# WL-RF-SWR.net
KiCad netlist of a schematic drawn in Altium Designer
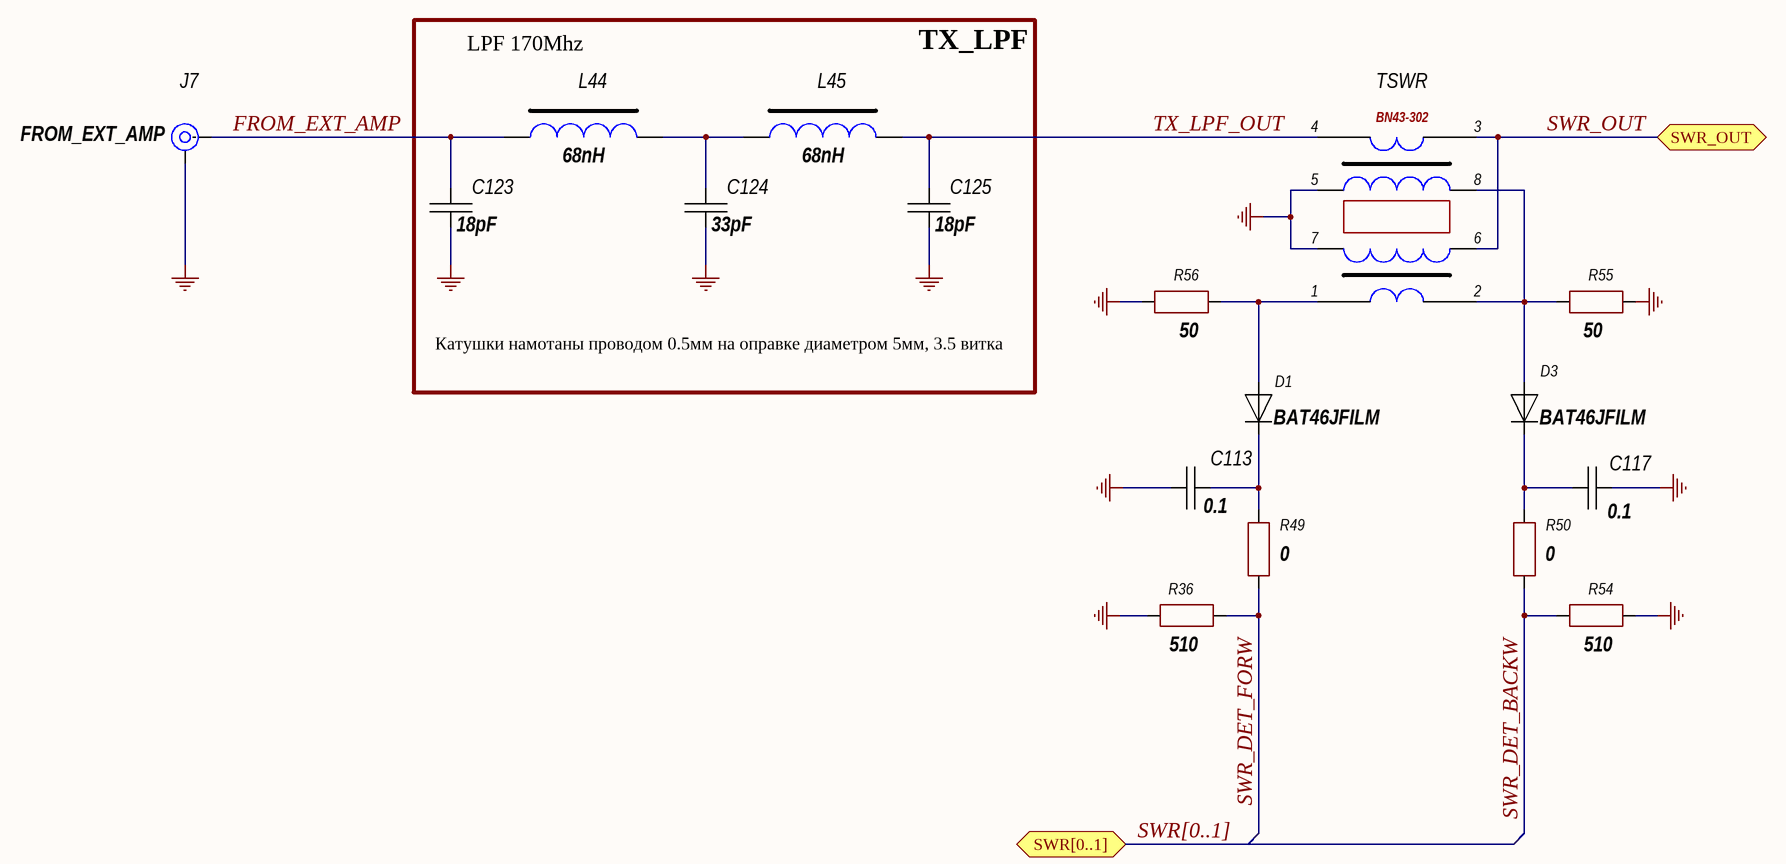
[diagram p0: WL-RF-SWR.SchDoc]

(export (version "E")
  (design (tool "Eeschema 10.0.6"))
  (components
    (comp (ref "C113")
      (value "0.1")
      (footprint "standard:CH0805C")
      (libsource (lib "Discrete") (part "Capacitor"))
    )
    (comp (ref "C117")
      (value "0.1")
      (footprint "standard:CH0805C")
      (libsource (lib "Discrete") (part "Capacitor"))
    )
    (comp (ref "C123")
      (value "18pF")
      (footprint "standard:CH0805C")
      (libsource (lib "Discrete") (part "Capacitor"))
    )
    (comp (ref "C124")
      (value "33pF")
      (footprint "standard:CH0805C")
      (libsource (lib "Discrete") (part "Capacitor"))
    )
    (comp (ref "C125")
      (value "18pF")
      (footprint "standard:CH0805C")
      (libsource (lib "Discrete") (part "Capacitor"))
    )
    (comp (ref "D1") (value "BAT46JFILM") (footprint "D9B") (libsource (lib "Diods") (part "Diod")))
    (comp (ref "D3") (value "BAT46JFILM") (footprint "D9B") (libsource (lib "Diods") (part "Diod")))
    (comp (ref "J7")
      (value "FROM_EXT_AMP")
      (footprint "custom:CON: SMA")
      (description "RF")
      (libsource (lib "Connectors") (part "SMA"))
    )
    (comp (ref "L44") (value "68nH") (libsource (lib "Transformers") (part "TRANS")))
    (comp (ref "L45") (value "68nH") (libsource (lib "Transformers") (part "TRANS")))
    (comp (ref "R36")
      (value "510")
      (footprint "standard:CH1206R")
      (libsource (lib "Discrete") (part "Resistor"))
    )
    (comp (ref "R49")
      (value "0")
      (footprint "standard:CH1206R")
      (libsource (lib "Discrete") (part "Resistor"))
    )
    (comp (ref "R50")
      (value "0")
      (footprint "standard:CH1206R")
      (libsource (lib "Discrete") (part "Resistor"))
    )
    (comp (ref "R54") (value "510") (footprint "standard:CH1206R") (libsource (lib "") (part "Resistor_1")))
    (comp (ref "R55") (value "50") (footprint "standard:CH1206R") (libsource (lib "") (part "Resistor_1")))
    (comp (ref "R56")
      (value "50")
      (footprint "standard:CH1206R")
      (libsource (lib "Discrete") (part "Resistor"))
    )
    (comp (ref "TSWR")
      (value "BN43-302")
      (footprint "TANDEM")
      (libsource (lib "Transformers") (part "BN43-302"))
    )
  )
  (nets
    (net (code "3") (name "/FROM_EXT_AMP") (class "Default")
      (node (ref "C123") (pin "2") (pinfunction "2_2") (pintype "power_in"))
      (node (ref "J7") (pin "1") (pinfunction "IN_1") (pintype "passive"))
      (node (ref "L44") (pin "1") (pinfunction "1_1") (pintype "power_in"))
    )
    (net (code "5") (name "/SWR_DET_BACKW") (class "Default")
      (node (ref "R50") (pin "1") (pinfunction "1_1") (pintype "passive"))
      (node (ref "R54") (pin "2") (pinfunction "2_2") (pintype "passive"))
    )
    (net (code "6") (name "/SWR_DET_FORW") (class "Default")
      (node (ref "R36") (pin "2") (pinfunction "2_2") (pintype "passive"))
      (node (ref "R49") (pin "1") (pinfunction "1_1") (pintype "passive"))
    )
    (net (code "7") (name "/SWR_OUT") (class "Default")
      (node (ref "TSWR") (pin "3") (pinfunction "3_3") (pintype "power_in"))
      (node (ref "TSWR") (pin "6") (pinfunction "6_6") (pintype "power_in"))
    )
    (net (code "8") (name "/TX_LPF_OUT") (class "Default")
      (node (ref "C125") (pin "2") (pinfunction "2_2") (pintype "power_in"))
      (node (ref "L45") (pin "2") (pinfunction "2_2") (pintype "power_in"))
      (node (ref "TSWR") (pin "4") (pinfunction "4_4") (pintype "power_in"))
    )
    (net (code "9") (name "GND") (class "Default")
      (node (ref "C113") (pin "1") (pinfunction "1_1") (pintype "power_in"))
      (node (ref "C117") (pin "1") (pinfunction "1_1") (pintype "power_in"))
      (node (ref "C123") (pin "1") (pinfunction "1_1") (pintype "power_in"))
      (node (ref "C124") (pin "1") (pinfunction "1_1") (pintype "power_in"))
      (node (ref "C125") (pin "1") (pinfunction "1_1") (pintype "power_in"))
      (node (ref "J7") (pin "2") (pinfunction "IN_2") (pintype "passive"))
      (node (ref "R36") (pin "1") (pinfunction "1_1") (pintype "passive"))
      (node (ref "R54") (pin "1") (pinfunction "1_1") (pintype "passive"))
      (node (ref "R55") (pin "1") (pinfunction "1_1") (pintype "passive"))
      (node (ref "R56") (pin "1") (pinfunction "1_1") (pintype "passive"))
      (node (ref "TSWR") (pin "5") (pinfunction "5_5") (pintype "power_in"))
      (node (ref "TSWR") (pin "7") (pinfunction "8_7") (pintype "power_in"))
    )
    (net (code "10") (name "Net-(C113-Pad2)") (class "Default")
      (node (ref "C113") (pin "2") (pinfunction "2_2") (pintype "power_in"))
      (node (ref "D1") (pin "2") (pinfunction "2_2") (pintype "passive"))
      (node (ref "R49") (pin "2") (pinfunction "2_2") (pintype "passive"))
    )
    (net (code "11") (name "Net-(C117-Pad2)") (class "Default")
      (node (ref "C117") (pin "2") (pinfunction "2_2") (pintype "power_in"))
      (node (ref "D3") (pin "2") (pinfunction "2_2") (pintype "passive"))
      (node (ref "R50") (pin "2") (pinfunction "2_2") (pintype "passive"))
    )
    (net (code "12") (name "Net-(C124-Pad2)") (class "Default")
      (node (ref "C124") (pin "2") (pinfunction "2_2") (pintype "power_in"))
      (node (ref "L44") (pin "2") (pinfunction "2_2") (pintype "power_in"))
      (node (ref "L45") (pin "1") (pinfunction "1_1") (pintype "power_in"))
    )
    (net (code "13") (name "Net-(D1-Pad1)") (class "Default")
      (node (ref "D1") (pin "1") (pinfunction "1_1") (pintype "passive"))
      (node (ref "R56") (pin "2") (pinfunction "2_2") (pintype "passive"))
      (node (ref "TSWR") (pin "1") (pinfunction "1_1") (pintype "power_in"))
    )
    (net (code "14") (name "Net-(D3-Pad1)") (class "Default")
      (node (ref "D3") (pin "1") (pinfunction "1_1") (pintype "passive"))
      (node (ref "R55") (pin "2") (pinfunction "2_2") (pintype "passive"))
      (node (ref "TSWR") (pin "2") (pinfunction "2_2") (pintype "power_in"))
      (node (ref "TSWR") (pin "8") (pinfunction "8_8") (pintype "power_in"))
    )
  )
)
